# SCH_relay-lite.net
KiCad netlist of a schematic drawn in EasyEDA
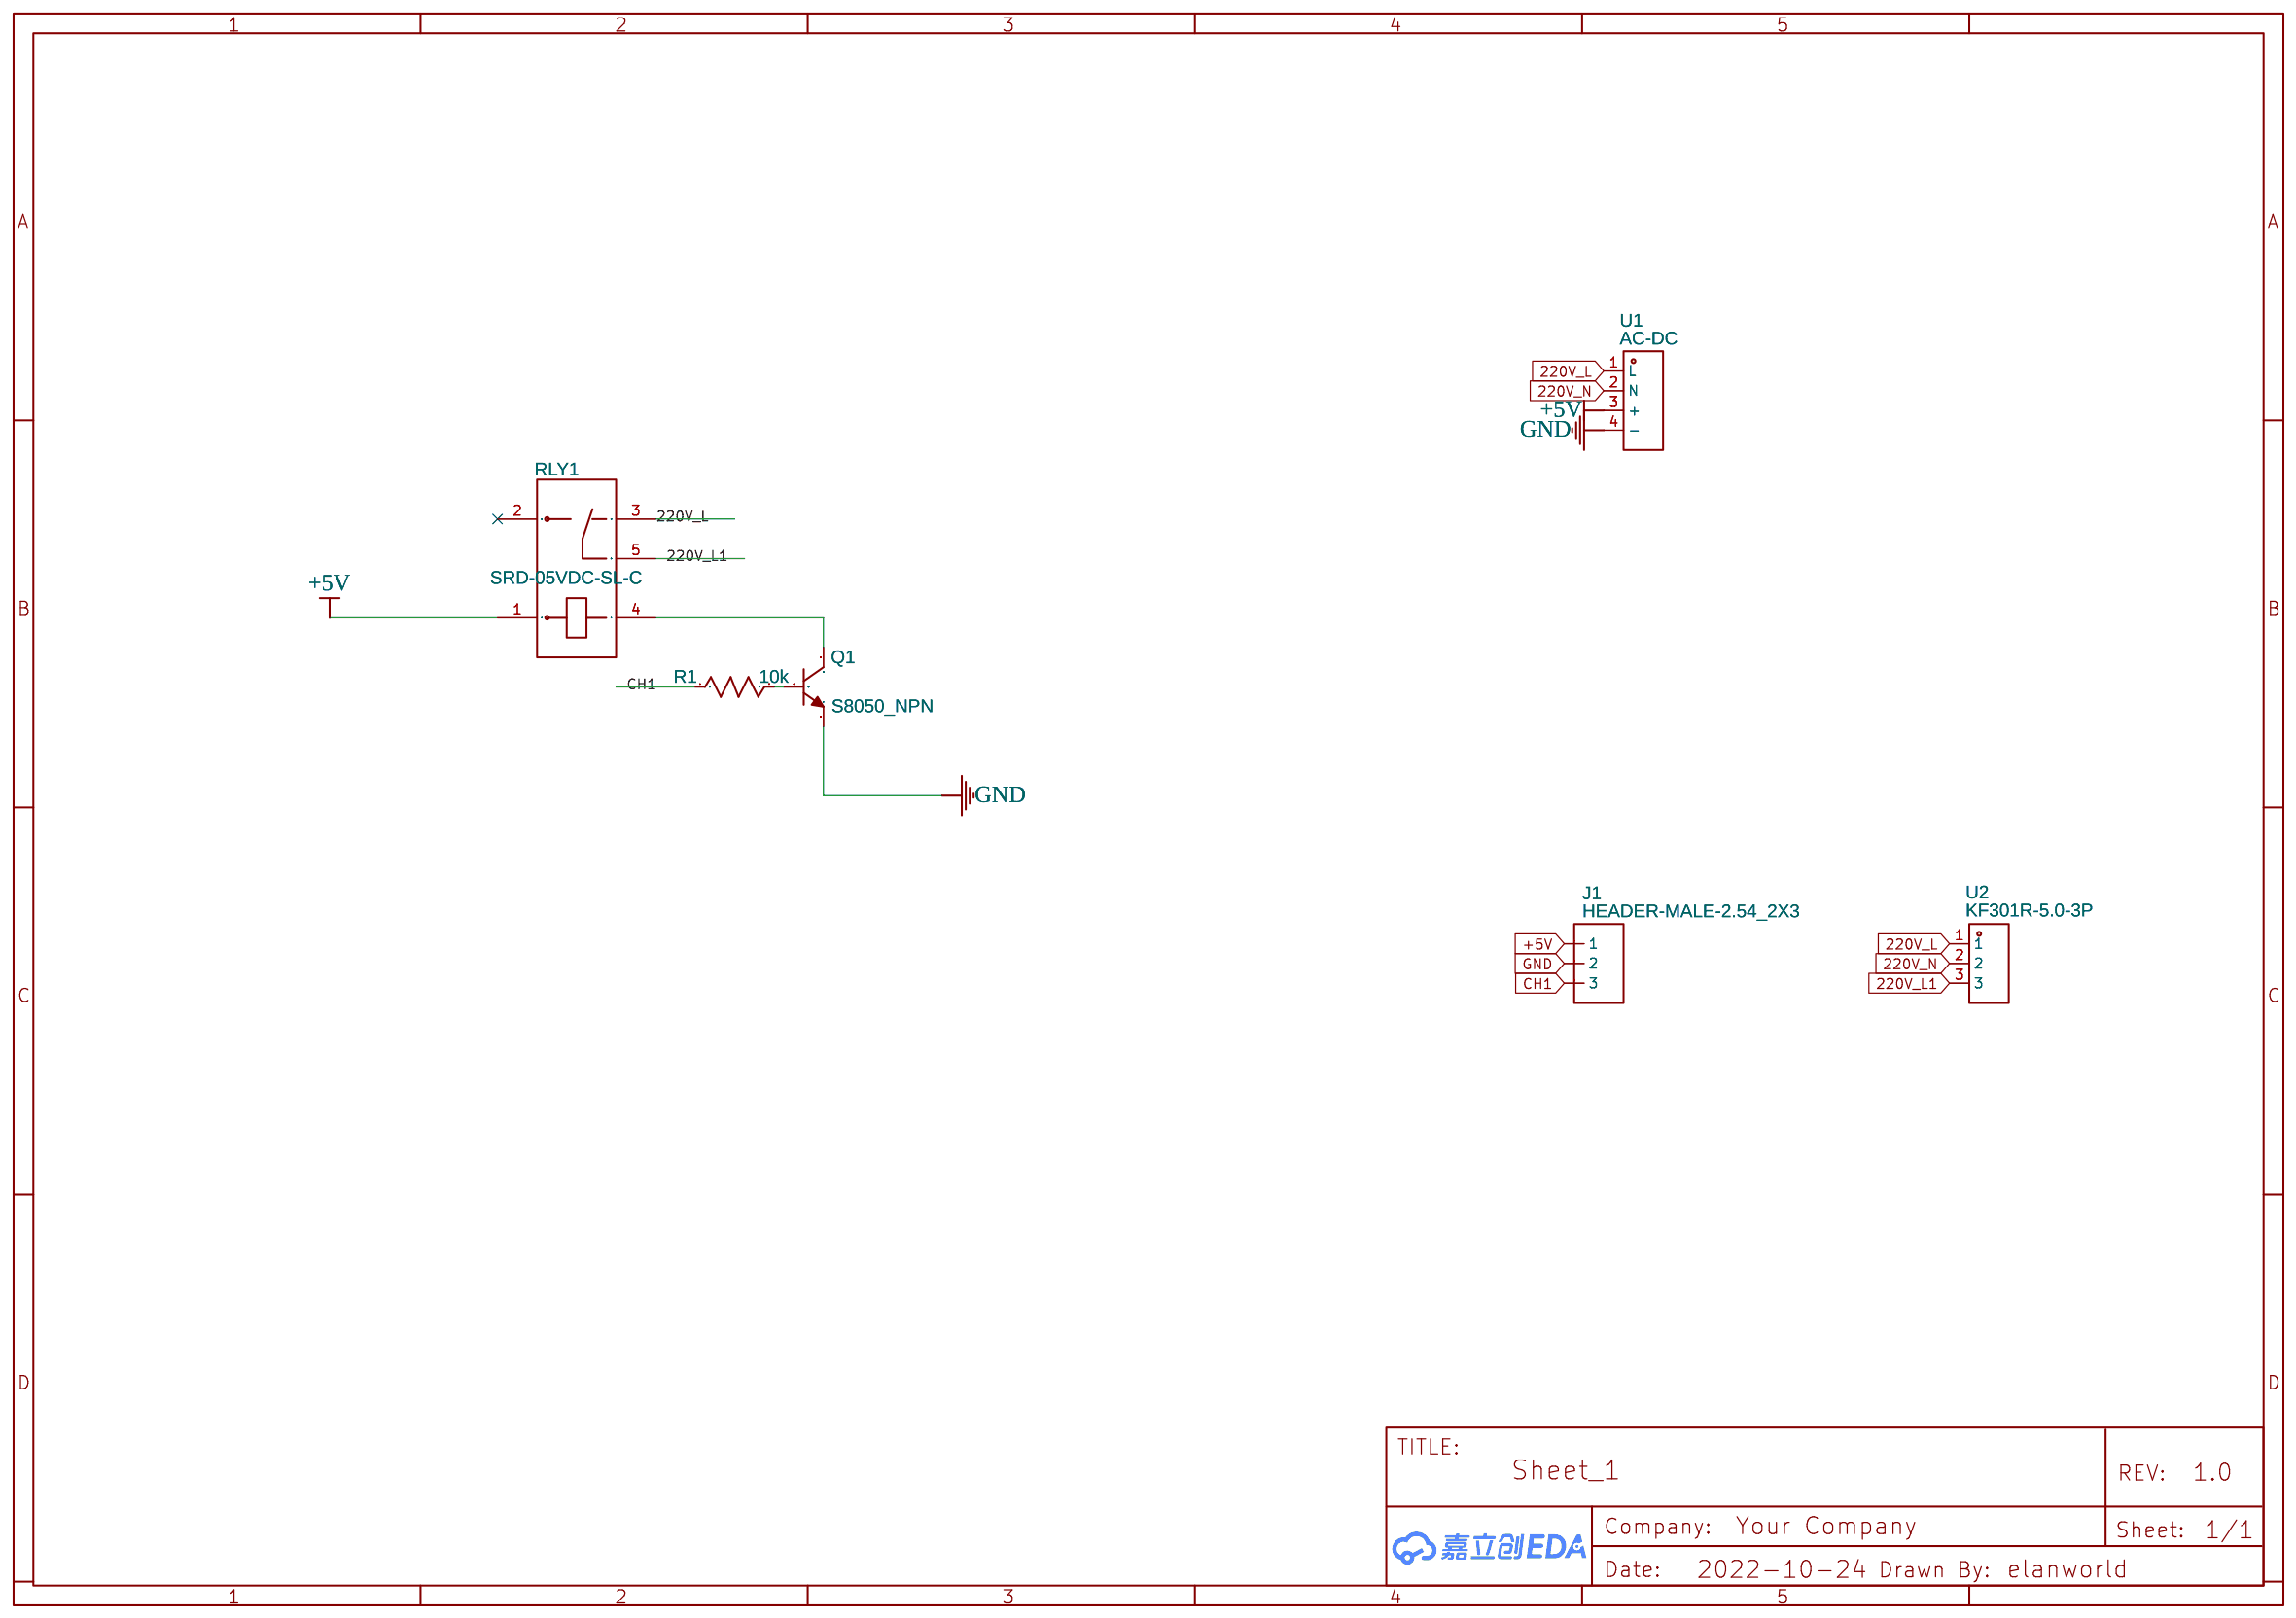
[diagram p0: schematic sheet]

(export (version "E")
  (design (tool "Eeschema 10.0.6"))
  (components
    (comp (ref "J1")
      (value "HEADER-MALE-2.54_2X3")
      (fields
        (field (name "BOM_Manufacturer Part") "Header-Male-2.54_2x3")
        (field (name "BOM_Supplier Part") "C65114")
      )
      (libsource (lib "") (part "HEADER-MALE-2.54_2X3"))
    )
    (comp (ref "Q1")
      (value "S8050_NPN")
      (fields (field (name "BOM_Manufacturer Part") "S8050") (field (name "BOM_Supplier Part") "C466625"))
      (libsource (lib "") (part "S8050_C466625"))
    )
    (comp (ref "R1") (value "10k") (libsource (lib "") (part "R_0603_US")))
    (comp (ref "RLY1")
      (value "SRD-05VDC-SL-C")
      (fields (field (name "BOM_Supplier Part") "C35449"))
      (libsource (lib "") (part "SRD-05VDC-SL-C"))
    )
    (comp (ref "U1") (value "AC-DC") (libsource (lib "") (part "AC-DC")))
    (comp (ref "U2")
      (value "KF301R-5.0-3P")
      (fields (field (name "BOM_Supplier Part") "C474884"))
      (libsource (lib "") (part "KF301R-5.0-3P"))
    )
  )
  (nets
    (net (code "1") (name "+5V") (class "Default")
      (node (ref "J1") (pin "1") (pinfunction "1_1") (pintype "input"))
      (node (ref "RLY1") (pin "1") (pinfunction "1_1") (pintype "input"))
      (node (ref "U1") (pin "3") (pinfunction "+_3") (pintype "unspecified"))
    )
    (net (code "2") (name "220V_L") (class "Default")
      (node (ref "RLY1") (pin "3") (pinfunction "3_3") (pintype "input"))
      (node (ref "U1") (pin "1") (pinfunction "L_1") (pintype "unspecified"))
      (node (ref "U2") (pin "1") (pinfunction "1_1") (pintype "unspecified"))
    )
    (net (code "3") (name "220V_L1") (class "Default")
      (node (ref "RLY1") (pin "5") (pinfunction "5_5") (pintype "input"))
      (node (ref "U2") (pin "3") (pinfunction "3_3") (pintype "unspecified"))
    )
    (net (code "4") (name "220V_N") (class "Default")
      (node (ref "U1") (pin "2") (pinfunction "N_2") (pintype "unspecified"))
      (node (ref "U2") (pin "2") (pinfunction "2_2") (pintype "unspecified"))
    )
    (net (code "5") (name "CH1") (class "Default")
      (node (ref "J1") (pin "3") (pinfunction "3_3") (pintype "input"))
      (node (ref "R1") (pin "1") (pinfunction "1_1") (pintype "unspecified"))
    )
    (net (code "6") (name "GND") (class "Default")
      (node (ref "J1") (pin "2") (pinfunction "2_2") (pintype "input"))
      (node (ref "Q1") (pin "2") (pinfunction "E_2") (pintype "unspecified"))
      (node (ref "U1") (pin "4") (pinfunction "-_4") (pintype "unspecified"))
    )
    (net (code "7") (name "Net-(Q1-B)") (class "Default")
      (node (ref "Q1") (pin "1") (pinfunction "B_1") (pintype "unspecified"))
      (node (ref "R1") (pin "2") (pinfunction "2_2") (pintype "unspecified"))
    )
    (net (code "8") (name "Net-(Q1-C)") (class "Default")
      (node (ref "Q1") (pin "3") (pinfunction "C_3") (pintype "unspecified"))
      (node (ref "RLY1") (pin "4") (pinfunction "4_4") (pintype "input"))
    )
    (net (code "9") (name "unconnected-(RLY1-Pad2)") (class "Default")
      (node (ref "RLY1") (pin "2") (pinfunction "2_2") (pintype "input+no_connect"))
    )
  )
)
